# ESP-OLED.net
KiCad netlist of a schematic drawn in Altium Designer
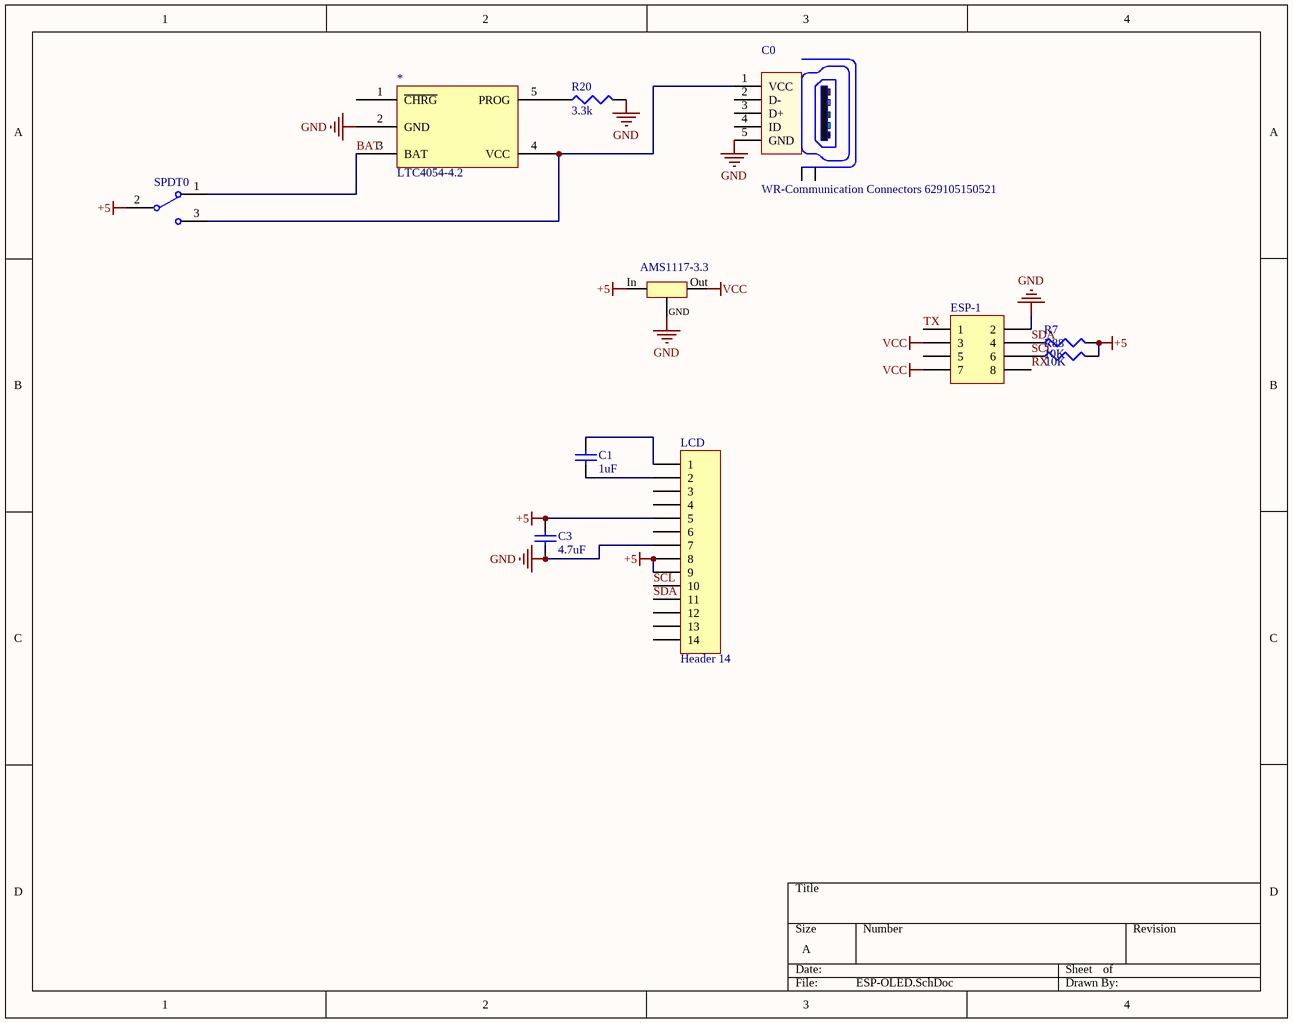
[diagram p0: ESP-OLED.SchDoc]

(export (version "E")
  (design (tool "Eeschema 10.0.6"))
  (components
    (comp (ref "*") (value "LTC4054-4.2") (footprint "S5") (libsource (lib "arad") (part "LTC4054-4.2")))
    (comp (ref "C0")
      (value "WR-Communication Connectors 629105150521")
      (footprint "arad:629105150521_no_fixtures")
      (description "WR-COM_USB_Micro Type B_Horizontal_SMT")
      (fields
        (field (name "MANUFACTURER") "Würth Elektronik eiSos GmbH")
        (field (name "PARTNO") "629105150521")
        (field (name "CREATED BY") "Karrer Zheng")
      )
      (libsource (lib "arad") (part "WR-Communication Connectors 629105150521"))
    )
    (comp (ref "C1")
      (value "1uF")
      (footprint "1608[0603]")
      (description "Capacitor (Semiconductor SIM Model)")
      (fields (field (name "Comment") "Cap Semi") (field (name "PUBLISHER") "Altium Limited"))
      (libsource (lib "Miscellaneous Devices") (part "Cap Semi"))
    )
    (comp (ref "C3")
      (value "4.7uF")
      (footprint "1608[0603]")
      (description "Capacitor (Semiconductor SIM Model)")
      (fields (field (name "Comment") "Cap Semi") (field (name "PUBLISHER") "Altium Limited"))
      (libsource (lib "Miscellaneous Devices") (part "Cap Semi"))
    )
    (comp (ref "ESP-1")
      (value "Header 4X2")
      (footprint "ESP-01")
      (description "Header, 4-Pin, Dual row")
      (fields (field (name "PUBLISHER") "Altium Limited"))
      (libsource (lib "Miscellaneous Connectors") (part "Header 4X2"))
    )
    (comp (ref "LCD")
      (value "Header 14")
      (footprint "arad:OLED0.49")
      (description "Header, 14-Pin")
      (fields (field (name "PUBLISHER") "Altium Limited"))
      (libsource (lib "Miscellaneous Connectors") (part "Header 14"))
    )
    (comp (ref "R7")
      (value "10K")
      (footprint "J1-0603")
      (description "Resistor")
      (fields (field (name "Comment") "Res3") (field (name "PUBLISHER") "Altium Limited"))
      (libsource (lib "Miscellaneous Devices") (part "Res3"))
    )
    (comp (ref "R20")
      (value "3.3k")
      (footprint "J1-0603")
      (description "Resistor")
      (fields (field (name "Comment") "Res3") (field (name "PUBLISHER") "Altium Limited"))
      (libsource (lib "Miscellaneous Devices") (part "Res3"))
    )
    (comp (ref "R88")
      (value "10K")
      (footprint "J1-0603")
      (description "Resistor")
      (fields (field (name "Comment") "Res3") (field (name "PUBLISHER") "Altium Limited"))
      (libsource (lib "Miscellaneous Devices") (part "Res3"))
    )
    (comp (ref "reg")
      (value "AMS1117-3.3")
      (footprint "SOT223")
      (libsource (lib "Diverse") (part "AMS1117-3.3"))
    )
    (comp (ref "SPDT0")
      (value "450404015514")
      (footprint "450404015514")
      (description "WS-SLSU Mini SMT Slide Switch, Same Side Connection, Right Angled, SPDT")
      (fields (field (name "PUBLISHER") "Wurth Elektronik"))
      (libsource (lib "arad") (part "450404015514"))
    )
  )
  (nets
    (net (code "1") (name "+5") (class "Default")
      (node (ref "C3") (pin "2") (pinfunction "2_2") (pintype "passive"))
      (node (ref "LCD") (pin "5") (pinfunction "5_5") (pintype "passive"))
      (node (ref "LCD") (pin "8") (pinfunction "8_8") (pintype "passive"))
      (node (ref "LCD") (pin "9") (pinfunction "9_9") (pintype "passive"))
      (node (ref "R7") (pin "2") (pinfunction "2_2") (pintype "passive"))
      (node (ref "R88") (pin "2") (pinfunction "2_2") (pintype "passive"))
      (node (ref "SPDT0") (pin "2") (pinfunction "COM_2") (pintype "passive"))
      (node (ref "reg") (pin "3") (pinfunction "3_3") (pintype "passive"))
    )
    (net (code "2") (name "/BAT") (class "Default")
      (node (ref "*") (pin "3") (pinfunction "BAT_3") (pintype "passive"))
      (node (ref "SPDT0") (pin "1") (pinfunction "1_1") (pintype "passive"))
    )
    (net (code "3") (name "/RX") (class "Default")
      (node (ref "ESP-1") (pin "8") (pinfunction "8_8") (pintype "passive"))
    )
    (net (code "4") (name "/SCL") (class "Default")
      (node (ref "ESP-1") (pin "6") (pinfunction "6_6") (pintype "passive"))
      (node (ref "LCD") (pin "10") (pinfunction "10_10") (pintype "passive"))
      (node (ref "R88") (pin "1") (pinfunction "1_1") (pintype "passive"))
    )
    (net (code "5") (name "/SDA") (class "Default")
      (node (ref "ESP-1") (pin "4") (pinfunction "4_4") (pintype "passive"))
      (node (ref "LCD") (pin "11") (pinfunction "11_11") (pintype "passive"))
      (node (ref "R7") (pin "1") (pinfunction "1_1") (pintype "passive"))
    )
    (net (code "6") (name "/TX") (class "Default")
      (node (ref "ESP-1") (pin "1") (pinfunction "1_1") (pintype "passive"))
    )
    (net (code "7") (name "GND") (class "Default")
      (node (ref "*") (pin "2") (pinfunction "GND_2") (pintype "passive"))
      (node (ref "C0") (pin "5") (pinfunction "GND_5") (pintype "passive"))
      (node (ref "C3") (pin "1") (pinfunction "1_1") (pintype "passive"))
      (node (ref "ESP-1") (pin "2") (pinfunction "2_2") (pintype "passive"))
      (node (ref "LCD") (pin "7") (pinfunction "7_7") (pintype "passive"))
      (node (ref "R20") (pin "2") (pinfunction "2_2") (pintype "passive"))
      (node (ref "reg") (pin "1") (pinfunction "1_1") (pintype "passive"))
    )
    (net (code "8") (name "Net-(*-PROG)") (class "Default")
      (node (ref "*") (pin "5") (pinfunction "PROG_5") (pintype "passive"))
      (node (ref "R20") (pin "1") (pinfunction "1_1") (pintype "passive"))
    )
    (net (code "9") (name "Net-(*-VCC)") (class "Default")
      (node (ref "*") (pin "4") (pinfunction "VCC_4") (pintype "passive"))
      (node (ref "C0") (pin "1") (pinfunction "VCC_1") (pintype "passive"))
      (node (ref "SPDT0") (pin "3") (pinfunction "3_3") (pintype "passive"))
    )
    (net (code "10") (name "Net-(C1-Pad1)") (class "Default")
      (node (ref "C1") (pin "1") (pinfunction "1_1") (pintype "passive"))
      (node (ref "LCD") (pin "2") (pinfunction "2_2") (pintype "passive"))
    )
    (net (code "11") (name "Net-(C1-Pad2)") (class "Default")
      (node (ref "C1") (pin "2") (pinfunction "2_2") (pintype "passive"))
      (node (ref "LCD") (pin "1") (pinfunction "1_1") (pintype "passive"))
    )
    (net (code "12") (name "VCC") (class "Default")
      (node (ref "ESP-1") (pin "3") (pinfunction "3_3") (pintype "passive"))
      (node (ref "ESP-1") (pin "7") (pinfunction "7_7") (pintype "passive"))
      (node (ref "reg") (pin "2") (pinfunction "2_2") (pintype "passive"))
    )
    (net (code "13") (name "unconnected-(*-~{CHRG}-Pad1)") (class "Default")
      (node (ref "*") (pin "1") (pinfunction "~{CHRG}_1") (pintype "passive"))
    )
    (net (code "14") (name "unconnected-(C0-D+-Pad3)") (class "Default")
      (node (ref "C0") (pin "3") (pinfunction "D+_3") (pintype "passive"))
    )
    (net (code "15") (name "unconnected-(C0-D--Pad2)") (class "Default")
      (node (ref "C0") (pin "2") (pinfunction "D-_2") (pintype "passive"))
    )
    (net (code "16") (name "unconnected-(C0-ID-Pad4)") (class "Default")
      (node (ref "C0") (pin "4") (pinfunction "ID_4") (pintype "passive"))
    )
    (net (code "17") (name "unconnected-(C0-Shield-PadZ1)") (class "Default")
      (node (ref "C0") (pin "Z1") (pinfunction "Shield_Z1") (pintype "passive"))
    )
    (net (code "18") (name "unconnected-(C0-Shield-PadZ2)") (class "Default")
      (node (ref "C0") (pin "Z2") (pinfunction "Shield_Z2") (pintype "passive"))
    )
    (net (code "19") (name "unconnected-(ESP-1-Pad5)") (class "Default")
      (node (ref "ESP-1") (pin "5") (pinfunction "5_5") (pintype "passive"))
    )
    (net (code "20") (name "unconnected-(LCD-Pad3)") (class "Default")
      (node (ref "LCD") (pin "3") (pinfunction "3_3") (pintype "passive"))
    )
    (net (code "21") (name "unconnected-(LCD-Pad4)") (class "Default")
      (node (ref "LCD") (pin "4") (pinfunction "4_4") (pintype "passive"))
    )
    (net (code "22") (name "unconnected-(LCD-Pad6)") (class "Default")
      (node (ref "LCD") (pin "6") (pinfunction "6_6") (pintype "passive"))
    )
    (net (code "23") (name "unconnected-(LCD-Pad12)") (class "Default")
      (node (ref "LCD") (pin "12") (pinfunction "12_12") (pintype "passive"))
    )
    (net (code "24") (name "unconnected-(LCD-Pad13)") (class "Default")
      (node (ref "LCD") (pin "13") (pinfunction "13_13") (pintype "passive"))
    )
    (net (code "25") (name "unconnected-(LCD-Pad14)") (class "Default")
      (node (ref "LCD") (pin "14") (pinfunction "14_14") (pintype "passive"))
    )
  )
)
